# mrna_badge_v1_2.net
KiCad netlist of a schematic drawn in EAGLE
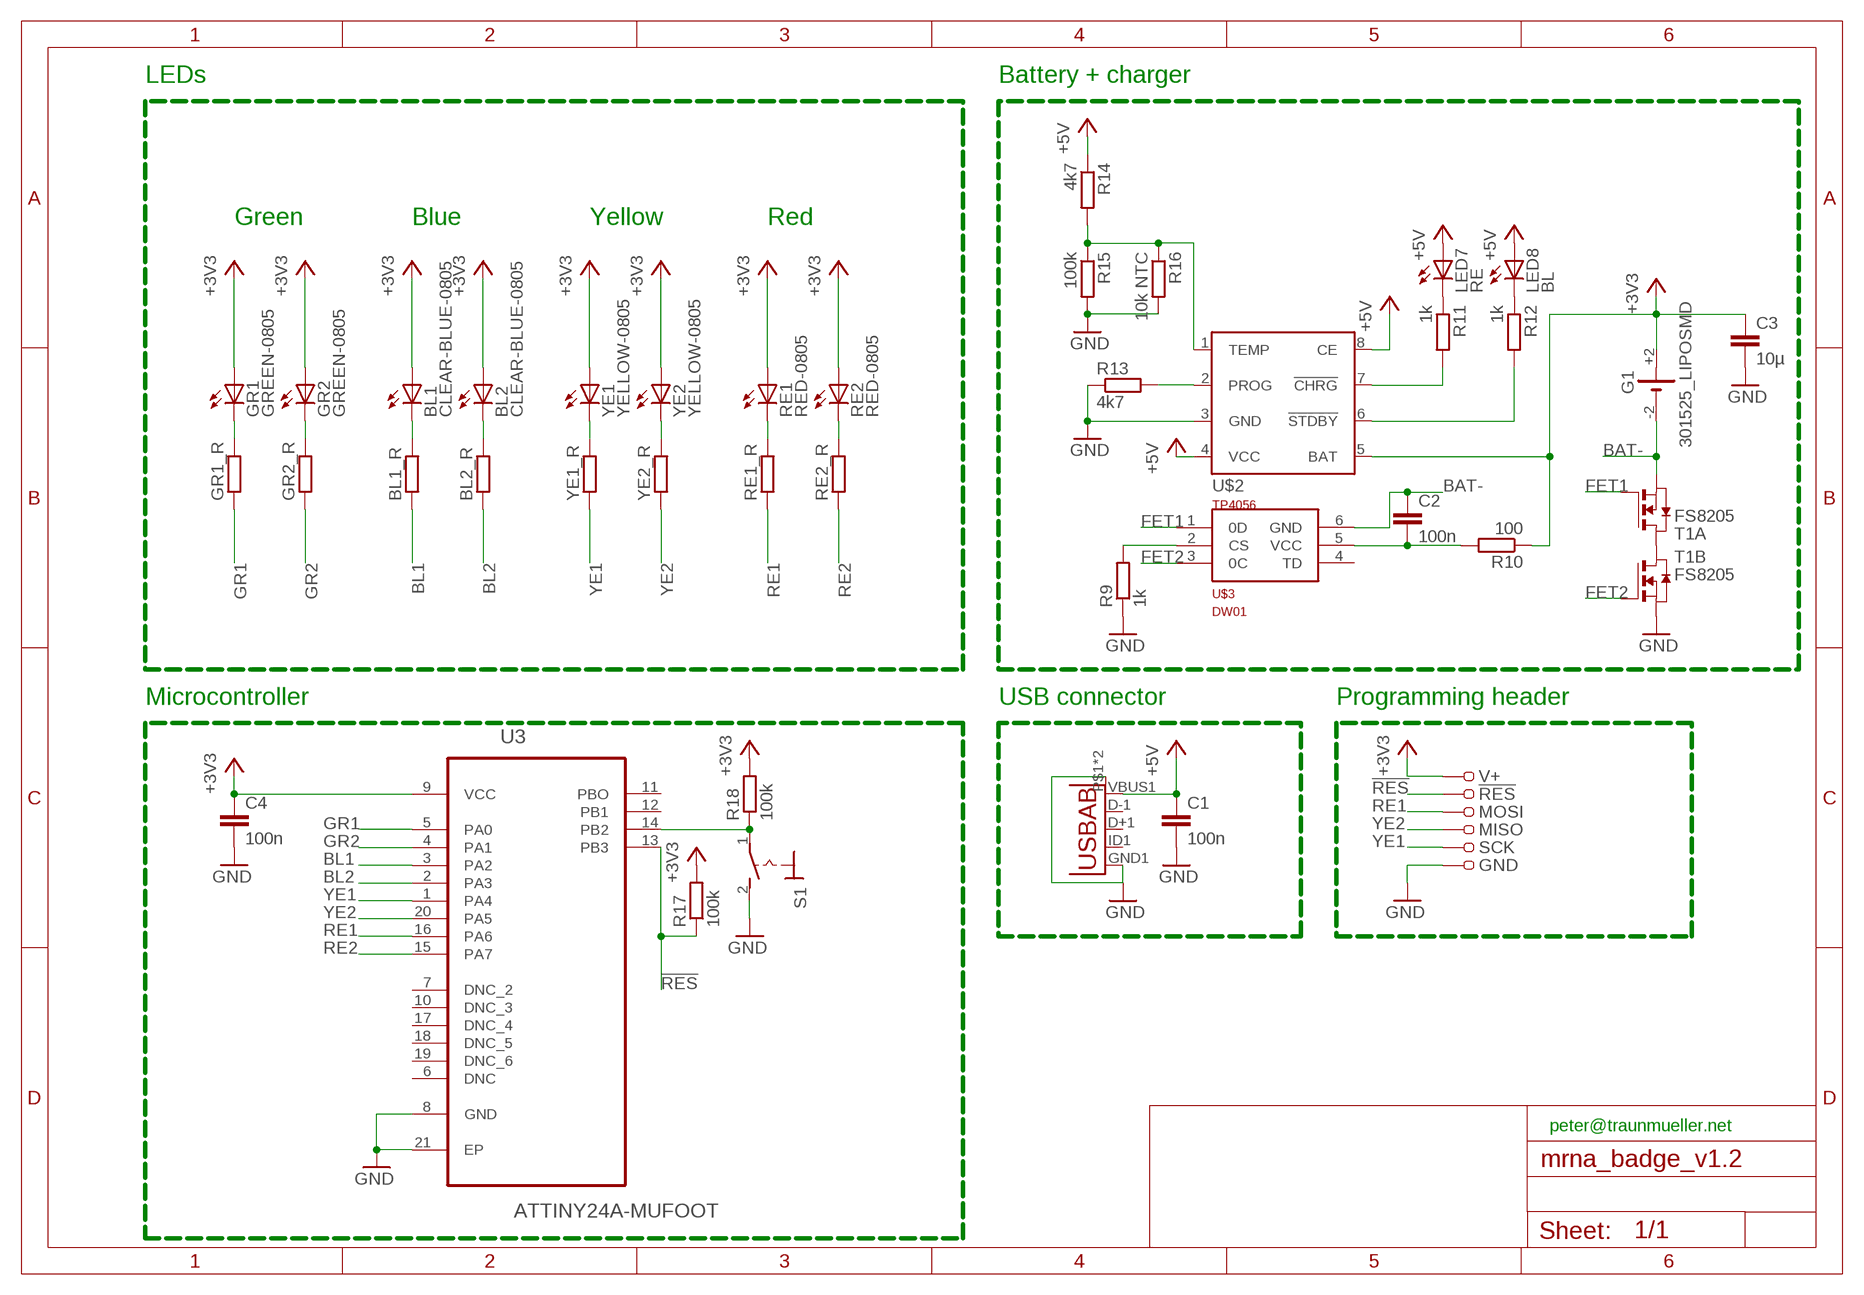
[diagram p0: schematic, sheet 1]

(export (version "E")
  (design (tool "Eeschema 10.0.6"))
  (components
    (comp (ref "!RES")
      (value "0.7MM_POGO-PINSPADS")
      (footprint "eagle-import:0.7MM_SMD_PADS")
      (libsource (lib "eagle-import") (part "0.7MM_POGO-PINSPADS"))
    )
    (comp (ref "BL1")
      (value "CLEAR-BLUE-0805")
      (footprint "eagle-import:CHIPLED_0805")
      (libsource (lib "eagle-import") (part "LEDCHIPLED_0805"))
    )
    (comp (ref "BL1_R")
      (value "R-EU_R0402")
      (footprint "eagle-import:R0402")
      (libsource (lib "eagle-import") (part "R-EU_R0402"))
    )
    (comp (ref "BL2")
      (value "CLEAR-BLUE-0805")
      (footprint "eagle-import:CHIPLED_0805")
      (libsource (lib "eagle-import") (part "LEDCHIPLED_0805"))
    )
    (comp (ref "BL2_R")
      (value "R-EU_R0402")
      (footprint "eagle-import:R0402")
      (libsource (lib "eagle-import") (part "R-EU_R0402"))
    )
    (comp (ref "C1")
      (value "100n")
      (footprint "eagle-import:C0402K")
      (libsource (lib "eagle-import") (part "C-EUC0402K"))
    )
    (comp (ref "C2")
      (value "100n")
      (footprint "eagle-import:C0402K")
      (libsource (lib "eagle-import") (part "C-EUC0402K"))
    )
    (comp (ref "C3")
      (value "10µ")
      (footprint "eagle-import:C0805K")
      (libsource (lib "eagle-import") (part "C-EUC0805K"))
    )
    (comp (ref "C4")
      (value "100n")
      (footprint "eagle-import:C0402K")
      (libsource (lib "eagle-import") (part "C-EUC0402K"))
    )
    (comp (ref "G1")
      (value "301525_LIPOSMD")
      (footprint "eagle-import:301525_LIPO_SMDCONTACTS")
      (libsource (lib "eagle-import") (part "301525_LIPOSMD"))
    )
    (comp (ref "GND")
      (value "0.7MM_POGO-PINSPADS")
      (footprint "eagle-import:0.7MM_SMD_PADS")
      (libsource (lib "eagle-import") (part "0.7MM_POGO-PINSPADS"))
    )
    (comp (ref "GR1")
      (value "GREEN-0805")
      (footprint "eagle-import:CHIPLED_0805")
      (libsource (lib "eagle-import") (part "LEDCHIPLED_0805"))
    )
    (comp (ref "GR1_R")
      (value "R-EU_R0402")
      (footprint "eagle-import:R0402")
      (libsource (lib "eagle-import") (part "R-EU_R0402"))
    )
    (comp (ref "GR2")
      (value "GREEN-0805")
      (footprint "eagle-import:CHIPLED_0805")
      (libsource (lib "eagle-import") (part "LEDCHIPLED_0805"))
    )
    (comp (ref "GR2_R")
      (value "R-EU_R0402")
      (footprint "eagle-import:R0402")
      (libsource (lib "eagle-import") (part "R-EU_R0402"))
    )
    (comp (ref "LED7")
      (value "RE")
      (footprint "eagle-import:CHIPLED_0603")
      (libsource (lib "eagle-import") (part "LEDCHIPLED_0603"))
    )
    (comp (ref "LED8")
      (value "BL")
      (footprint "eagle-import:CHIPLED_0603")
      (libsource (lib "eagle-import") (part "LEDCHIPLED_0603"))
    )
    (comp (ref "MISO")
      (value "0.7MM_POGO-PINSPADS")
      (footprint "eagle-import:0.7MM_SMD_PADS")
      (libsource (lib "eagle-import") (part "0.7MM_POGO-PINSPADS"))
    )
    (comp (ref "MOSI")
      (value "0.7MM_POGO-PINSPADS")
      (footprint "eagle-import:0.7MM_SMD_PADS")
      (libsource (lib "eagle-import") (part "0.7MM_POGO-PINSPADS"))
    )
    (comp (ref "R9")
      (value "1k")
      (footprint "eagle-import:R0402")
      (libsource (lib "eagle-import") (part "R-EU_R0402"))
    )
    (comp (ref "R10")
      (value "100")
      (footprint "eagle-import:R0402")
      (libsource (lib "eagle-import") (part "R-EU_R0402"))
    )
    (comp (ref "R11")
      (value "1k")
      (footprint "eagle-import:R0402")
      (libsource (lib "eagle-import") (part "R-EU_R0402"))
    )
    (comp (ref "R12")
      (value "1k")
      (footprint "eagle-import:R0402")
      (libsource (lib "eagle-import") (part "R-EU_R0402"))
    )
    (comp (ref "R13")
      (value "4k7")
      (footprint "eagle-import:R0402")
      (libsource (lib "eagle-import") (part "R-EU_R0402"))
    )
    (comp (ref "R14")
      (value "4k7")
      (footprint "eagle-import:R0402")
      (libsource (lib "eagle-import") (part "R-EU_R0402"))
    )
    (comp (ref "R15")
      (value "100k")
      (footprint "eagle-import:R0402")
      (libsource (lib "eagle-import") (part "R-EU_R0402"))
    )
    (comp (ref "R16")
      (value "10k NTC")
      (footprint "eagle-import:R0805")
      (libsource (lib "eagle-import") (part "R-EU_R0805"))
    )
    (comp (ref "R17")
      (value "100k")
      (footprint "eagle-import:R0402")
      (libsource (lib "eagle-import") (part "R-EU_R0402"))
    )
    (comp (ref "R18")
      (value "100k")
      (footprint "eagle-import:R0402")
      (libsource (lib "eagle-import") (part "R-EU_R0402"))
    )
    (comp (ref "RE1")
      (value "RED-0805")
      (footprint "eagle-import:CHIPLED_0805")
      (libsource (lib "eagle-import") (part "LEDCHIPLED_0805"))
    )
    (comp (ref "RE1_R")
      (value "R-EU_R0402")
      (footprint "eagle-import:R0402")
      (libsource (lib "eagle-import") (part "R-EU_R0402"))
    )
    (comp (ref "RE2")
      (value "RED-0805")
      (footprint "eagle-import:CHIPLED_0805")
      (libsource (lib "eagle-import") (part "LEDCHIPLED_0805"))
    )
    (comp (ref "RE2_R")
      (value "R-EU_R0402")
      (footprint "eagle-import:R0402")
      (libsource (lib "eagle-import") (part "R-EU_R0402"))
    )
    (comp (ref "S1")
      (value "TS-1088NOHOLES")
      (footprint "eagle-import:TS-1088_NOHOLES")
      (libsource (lib "eagle-import") (part "TS-1088NOHOLES"))
    )
    (comp (ref "SCK")
      (value "0.7MM_POGO-PINSPADS")
      (footprint "eagle-import:0.7MM_SMD_PADS")
      (libsource (lib "eagle-import") (part "0.7MM_POGO-PINSPADS"))
    )
    (comp (ref "T1")
      (value "FS8205")
      (footprint "eagle-import:TSSOP-8")
      (libsource (lib "eagle-import") (part "DMN3024LSD"))
    )
    (comp (ref "U$2")
      (value "TP4056ESOP")
      (footprint "eagle-import:ESOP23-8")
      (libsource (lib "eagle-import") (part "TP4056ESOP"))
    )
    (comp (ref "U$3")
      (value "DW01")
      (footprint "eagle-import:SOT23-6")
      (libsource (lib "eagle-import") (part "DW01"))
    )
    (comp (ref "U2")
      (value "USB\"\"")
      (footprint "eagle-import:USB-MICRO-SMD")
      (libsource (lib "eagle-import") (part "USB{dblquote}{dblquote}"))
    )
    (comp (ref "U3")
      (value "ATTINY24A-MUFOOT")
      (footprint "eagle-import:QFN50P400X400X80-21N_FOOTPRINT")
      (libsource (lib "eagle-import") (part "ATTINY24A-MUFOOT"))
    )
    (comp (ref "V+")
      (value "0.7MM_POGO-PINSPADS")
      (footprint "eagle-import:0.7MM_SMD_PADS")
      (libsource (lib "eagle-import") (part "0.7MM_POGO-PINSPADS"))
    )
    (comp (ref "YE1")
      (value "YELLOW-0805")
      (footprint "eagle-import:CHIPLED_0805")
      (libsource (lib "eagle-import") (part "LEDCHIPLED_0805"))
    )
    (comp (ref "YE1_R")
      (value "R-EU_R0402")
      (footprint "eagle-import:R0402")
      (libsource (lib "eagle-import") (part "R-EU_R0402"))
    )
    (comp (ref "YE2")
      (value "YELLOW-0805")
      (footprint "eagle-import:CHIPLED_0805")
      (libsource (lib "eagle-import") (part "LEDCHIPLED_0805"))
    )
    (comp (ref "YE2_R")
      (value "R-EU_R0402")
      (footprint "eagle-import:R0402")
      (libsource (lib "eagle-import") (part "R-EU_R0402"))
    )
  )
  (nets
    (net (code "1") (name "+3V3") (class "Default")
      (node (ref "BL1") (pin "A") (pinfunction "A_A") (pintype "passive"))
      (node (ref "BL2") (pin "A") (pinfunction "A_A") (pintype "passive"))
      (node (ref "C3") (pin "1") (pinfunction "1_1") (pintype "passive"))
      (node (ref "C4") (pin "1") (pinfunction "1_1") (pintype "passive"))
      (node (ref "G1") (pin "+2") (pinfunction "+_+2") (pintype "passive"))
      (node (ref "GR1") (pin "A") (pinfunction "A_A") (pintype "passive"))
      (node (ref "GR2") (pin "A") (pinfunction "A_A") (pintype "passive"))
      (node (ref "R10") (pin "1") (pinfunction "1_1") (pintype "passive"))
      (node (ref "R17") (pin "2") (pinfunction "2_2") (pintype "passive"))
      (node (ref "R18") (pin "2") (pinfunction "2_2") (pintype "passive"))
      (node (ref "RE1") (pin "A") (pinfunction "A_A") (pintype "passive"))
      (node (ref "RE2") (pin "A") (pinfunction "A_A") (pintype "passive"))
      (node (ref "U$2") (pin "5") (pinfunction "BAT_5") (pintype "bidirectional"))
      (node (ref "U3") (pin "9") (pinfunction "VCC_9") (pintype "power_in"))
      (node (ref "V+") (pin "P$1") (pinfunction "1_P$1") (pintype "passive"))
      (node (ref "YE1") (pin "A") (pinfunction "A_A") (pintype "passive"))
      (node (ref "YE2") (pin "A") (pinfunction "A_A") (pintype "passive"))
    )
    (net (code "2") (name "+5V") (class "Default")
      (node (ref "C1") (pin "1") (pinfunction "1_1") (pintype "passive"))
      (node (ref "LED7") (pin "A") (pinfunction "A_A") (pintype "passive"))
      (node (ref "LED8") (pin "A") (pinfunction "A_A") (pintype "passive"))
      (node (ref "R14") (pin "1") (pinfunction "1_1") (pintype "passive"))
      (node (ref "U$2") (pin "4") (pinfunction "VCC_4") (pintype "bidirectional"))
      (node (ref "U$2") (pin "8") (pinfunction "CE_8") (pintype "bidirectional"))
      (node (ref "U2") (pin "VBUS1") (pinfunction "VBUS_VBUS1") (pintype "bidirectional"))
    )
    (net (code "3") (name "/BAT-") (class "Default")
      (node (ref "C2") (pin "1") (pinfunction "1_1") (pintype "passive"))
      (node (ref "G1") (pin "-2") (pinfunction "-_-2") (pintype "passive"))
      (node (ref "T1") (pin "2") (pinfunction "S_2") (pintype "passive"))
      (node (ref "T1") (pin "3") (pinfunction "S_3") (pintype "passive"))
      (node (ref "U$3") (pin "6") (pinfunction "GND_6") (pintype "bidirectional"))
    )
    (net (code "4") (name "/BL1") (class "Default")
      (node (ref "BL1_R") (pin "1") (pinfunction "1_1") (pintype "passive"))
      (node (ref "U3") (pin "3") (pinfunction "PA2_3") (pintype "bidirectional"))
    )
    (net (code "5") (name "/BL2") (class "Default")
      (node (ref "BL2_R") (pin "1") (pinfunction "1_1") (pintype "passive"))
      (node (ref "U3") (pin "2") (pinfunction "PA3_2") (pintype "bidirectional"))
    )
    (net (code "6") (name "/FET1") (class "Default")
      (node (ref "T1") (pin "4") (pinfunction "G_4") (pintype "passive"))
      (node (ref "U$3") (pin "1") (pinfunction "0D_1") (pintype "bidirectional"))
    )
    (net (code "7") (name "/FET2") (class "Default")
      (node (ref "T1") (pin "5") (pinfunction "G_5") (pintype "passive"))
      (node (ref "U$3") (pin "3") (pinfunction "0C_3") (pintype "bidirectional"))
    )
    (net (code "8") (name "/GR1") (class "Default")
      (node (ref "GR1_R") (pin "1") (pinfunction "1_1") (pintype "passive"))
      (node (ref "U3") (pin "5") (pinfunction "PA0_5") (pintype "bidirectional"))
    )
    (net (code "9") (name "/GR2") (class "Default")
      (node (ref "GR2_R") (pin "1") (pinfunction "1_1") (pintype "passive"))
      (node (ref "U3") (pin "4") (pinfunction "PA1_4") (pintype "bidirectional"))
    )
    (net (code "11") (name "/RE1") (class "Default")
      (node (ref "MOSI") (pin "P$1") (pinfunction "1_P$1") (pintype "passive"))
      (node (ref "RE1_R") (pin "1") (pinfunction "1_1") (pintype "passive"))
      (node (ref "U3") (pin "16") (pinfunction "PA6_16") (pintype "bidirectional"))
    )
    (net (code "12") (name "/RE2") (class "Default")
      (node (ref "RE2_R") (pin "1") (pinfunction "1_1") (pintype "passive"))
      (node (ref "U3") (pin "15") (pinfunction "PA7_15") (pintype "bidirectional"))
    )
    (net (code "13") (name "/YE1") (class "Default")
      (node (ref "SCK") (pin "P$1") (pinfunction "1_P$1") (pintype "passive"))
      (node (ref "U3") (pin "1") (pinfunction "PA4_1") (pintype "bidirectional"))
      (node (ref "YE1_R") (pin "1") (pinfunction "1_1") (pintype "passive"))
    )
    (net (code "14") (name "/YE2") (class "Default")
      (node (ref "MISO") (pin "P$1") (pinfunction "1_P$1") (pintype "passive"))
      (node (ref "U3") (pin "20") (pinfunction "PA5_20") (pintype "bidirectional"))
      (node (ref "YE2_R") (pin "1") (pinfunction "1_1") (pintype "passive"))
    )
    (net (code "15") (name "/~{RES}") (class "Default")
      (node (ref "!RES") (pin "P$1") (pinfunction "1_P$1") (pintype "passive"))
      (node (ref "R17") (pin "1") (pinfunction "1_1") (pintype "passive"))
      (node (ref "U3") (pin "13") (pinfunction "PB3_13") (pintype "bidirectional"))
    )
    (net (code "16") (name "GND") (class "Default")
      (node (ref "C1") (pin "2") (pinfunction "2_2") (pintype "passive"))
      (node (ref "C3") (pin "2") (pinfunction "2_2") (pintype "passive"))
      (node (ref "C4") (pin "2") (pinfunction "2_2") (pintype "passive"))
      (node (ref "GND") (pin "P$1") (pinfunction "1_P$1") (pintype "passive"))
      (node (ref "R13") (pin "1") (pinfunction "1_1") (pintype "passive"))
      (node (ref "R15") (pin "2") (pinfunction "2_2") (pintype "passive"))
      (node (ref "R16") (pin "2") (pinfunction "2_2") (pintype "passive"))
      (node (ref "R9") (pin "1") (pinfunction "1_1") (pintype "passive"))
      (node (ref "S1") (pin "2") (pinfunction "S_2") (pintype "passive"))
      (node (ref "T1") (pin "6") (pinfunction "S_6") (pintype "passive"))
      (node (ref "T1") (pin "7") (pinfunction "S_7") (pintype "passive"))
      (node (ref "U$2") (pin "3") (pinfunction "GND_3") (pintype "bidirectional"))
      (node (ref "U2") (pin "GND1") (pinfunction "GND_GND1") (pintype "bidirectional"))
      (node (ref "U2") (pin "P$1") (pinfunction "CASE_P$1") (pintype "bidirectional"))
      (node (ref "U2") (pin "P$2") (pinfunction "CASE_P$2") (pintype "bidirectional"))
      (node (ref "U3") (pin "21") (pinfunction "EP_21") (pintype "passive"))
      (node (ref "U3") (pin "8") (pinfunction "GND_8") (pintype "passive"))
    )
    (net (code "17") (name "Net-(BL1-PadC)") (class "Default")
      (node (ref "BL1") (pin "C") (pinfunction "C_C") (pintype "passive"))
      (node (ref "BL1_R") (pin "2") (pinfunction "2_2") (pintype "passive"))
    )
    (net (code "18") (name "Net-(BL2-PadC)") (class "Default")
      (node (ref "BL2") (pin "C") (pinfunction "C_C") (pintype "passive"))
      (node (ref "BL2_R") (pin "2") (pinfunction "2_2") (pintype "passive"))
    )
    (net (code "19") (name "Net-(GR1-PadC)") (class "Default")
      (node (ref "GR1") (pin "C") (pinfunction "C_C") (pintype "passive"))
      (node (ref "GR1_R") (pin "2") (pinfunction "2_2") (pintype "passive"))
    )
    (net (code "20") (name "Net-(GR2-PadC)") (class "Default")
      (node (ref "GR2") (pin "C") (pinfunction "C_C") (pintype "passive"))
      (node (ref "GR2_R") (pin "2") (pinfunction "2_2") (pintype "passive"))
    )
    (net (code "21") (name "Net-(LED7-PadC)") (class "Default")
      (node (ref "LED7") (pin "C") (pinfunction "C_C") (pintype "passive"))
      (node (ref "R11") (pin "1") (pinfunction "1_1") (pintype "passive"))
    )
    (net (code "22") (name "Net-(LED8-PadC)") (class "Default")
      (node (ref "LED8") (pin "C") (pinfunction "C_C") (pintype "passive"))
      (node (ref "R12") (pin "1") (pinfunction "1_1") (pintype "passive"))
    )
    (net (code "23") (name "Net-(RE1-PadC)") (class "Default")
      (node (ref "RE1") (pin "C") (pinfunction "C_C") (pintype "passive"))
      (node (ref "RE1_R") (pin "2") (pinfunction "2_2") (pintype "passive"))
    )
    (net (code "24") (name "Net-(RE2-PadC)") (class "Default")
      (node (ref "RE2") (pin "C") (pinfunction "C_C") (pintype "passive"))
      (node (ref "RE2_R") (pin "2") (pinfunction "2_2") (pintype "passive"))
    )
    (net (code "25") (name "Net-(S1-P)") (class "Default")
      (node (ref "R18") (pin "1") (pinfunction "1_1") (pintype "passive"))
      (node (ref "S1") (pin "1") (pinfunction "P_1") (pintype "passive"))
      (node (ref "U3") (pin "14") (pinfunction "PB2_14") (pintype "bidirectional"))
    )
    (net (code "26") (name "Net-(T1A-D)") (class "Default")
      (node (ref "T1") (pin "1") (pinfunction "D_1") (pintype "passive"))
      (node (ref "T1") (pin "8") (pinfunction "D_8") (pintype "passive"))
    )
    (net (code "27") (name "Net-(U$2-PROG)") (class "Default")
      (node (ref "R13") (pin "2") (pinfunction "2_2") (pintype "passive"))
      (node (ref "U$2") (pin "2") (pinfunction "PROG_2") (pintype "bidirectional"))
    )
    (net (code "28") (name "Net-(U$2-TEMP)") (class "Default")
      (node (ref "R14") (pin "2") (pinfunction "2_2") (pintype "passive"))
      (node (ref "R15") (pin "1") (pinfunction "1_1") (pintype "passive"))
      (node (ref "R16") (pin "1") (pinfunction "1_1") (pintype "passive"))
      (node (ref "U$2") (pin "1") (pinfunction "TEMP_1") (pintype "bidirectional"))
    )
    (net (code "29") (name "Net-(U$2-~{CHRG})") (class "Default")
      (node (ref "R11") (pin "2") (pinfunction "2_2") (pintype "passive"))
      (node (ref "U$2") (pin "7") (pinfunction "~{CHRG}_7") (pintype "bidirectional"))
    )
    (net (code "30") (name "Net-(U$2-~{STDBY})") (class "Default")
      (node (ref "R12") (pin "2") (pinfunction "2_2") (pintype "passive"))
      (node (ref "U$2") (pin "6") (pinfunction "~{STDBY}_6") (pintype "bidirectional"))
    )
    (net (code "31") (name "Net-(U$3-CS)") (class "Default")
      (node (ref "R9") (pin "2") (pinfunction "2_2") (pintype "passive"))
      (node (ref "U$3") (pin "2") (pinfunction "CS_2") (pintype "bidirectional"))
    )
    (net (code "32") (name "Net-(U$3-VCC)") (class "Default")
      (node (ref "C2") (pin "2") (pinfunction "2_2") (pintype "passive"))
      (node (ref "R10") (pin "2") (pinfunction "2_2") (pintype "passive"))
      (node (ref "U$3") (pin "5") (pinfunction "VCC_5") (pintype "bidirectional"))
    )
    (net (code "33") (name "Net-(YE1-PadC)") (class "Default")
      (node (ref "YE1") (pin "C") (pinfunction "C_C") (pintype "passive"))
      (node (ref "YE1_R") (pin "2") (pinfunction "2_2") (pintype "passive"))
    )
    (net (code "34") (name "Net-(YE2-PadC)") (class "Default")
      (node (ref "YE2") (pin "C") (pinfunction "C_C") (pintype "passive"))
      (node (ref "YE2_R") (pin "2") (pinfunction "2_2") (pintype "passive"))
    )
    (net (code "35") (name "unconnected-(U$3-TD-Pad4)") (class "Default")
      (node (ref "U$3") (pin "4") (pinfunction "TD_4") (pintype "bidirectional"))
    )
    (net (code "36") (name "unconnected-(U2-D+-PadD+1)") (class "Default")
      (node (ref "U2") (pin "D+1") (pinfunction "D+_D+1") (pintype "bidirectional"))
    )
    (net (code "37") (name "unconnected-(U2-D--PadD-1)") (class "Default")
      (node (ref "U2") (pin "D-1") (pinfunction "D-_D-1") (pintype "bidirectional"))
    )
    (net (code "38") (name "unconnected-(U2-USBID-PadID1)") (class "Default")
      (node (ref "U2") (pin "ID1") (pinfunction "USBID_ID1") (pintype "bidirectional"))
    )
    (net (code "39") (name "unconnected-(U3-DNC-Pad6)") (class "Default")
      (node (ref "U3") (pin "6") (pinfunction "DNC_6") (pintype "no_connect"))
    )
    (net (code "40") (name "unconnected-(U3-DNC_2-Pad7)") (class "Default")
      (node (ref "U3") (pin "7") (pinfunction "DNC_2_7") (pintype "no_connect"))
    )
    (net (code "41") (name "unconnected-(U3-DNC_3-Pad10)") (class "Default")
      (node (ref "U3") (pin "10") (pinfunction "DNC_3_10") (pintype "no_connect"))
    )
    (net (code "42") (name "unconnected-(U3-DNC_4-Pad17)") (class "Default")
      (node (ref "U3") (pin "17") (pinfunction "DNC_4_17") (pintype "no_connect"))
    )
    (net (code "43") (name "unconnected-(U3-DNC_5-Pad18)") (class "Default")
      (node (ref "U3") (pin "18") (pinfunction "DNC_5_18") (pintype "no_connect"))
    )
    (net (code "44") (name "unconnected-(U3-DNC_6-Pad19)") (class "Default")
      (node (ref "U3") (pin "19") (pinfunction "DNC_6_19") (pintype "no_connect"))
    )
    (net (code "45") (name "unconnected-(U3-PB1-Pad12)") (class "Default")
      (node (ref "U3") (pin "12") (pinfunction "PB1_12") (pintype "bidirectional"))
    )
    (net (code "46") (name "unconnected-(U3-PBO-Pad11)") (class "Default")
      (node (ref "U3") (pin "11") (pinfunction "PBO_11") (pintype "bidirectional"))
    )
  )
)
